# relay.net
KiCad netlist of a schematic drawn in EAGLE
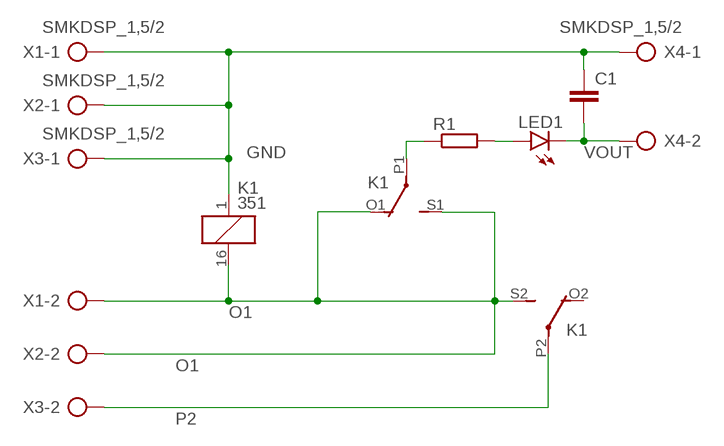
[diagram p0: schematic, sheet 1]

(export (version "E")
  (design (tool "Eeschema 10.0.6"))
  (components
    (comp (ref "C1")
      (value "C-EU025-025X050")
      (footprint "eagle-import:C025-025X050")
      (libsource (lib "eagle-import") (part "C-EU025-025X050"))
    )
    (comp (ref "K1")
      (value "351")
      (footprint "eagle-import:351")
      (libsource (lib "eagle-import") (part "351"))
    )
    (comp (ref "LED1")
      (value "LED3MM")
      (footprint "eagle-import:LED3MM")
      (libsource (lib "eagle-import") (part "LED3MM"))
    )
    (comp (ref "R1")
      (value "R-EU_0207/10")
      (footprint "eagle-import:0207_10")
      (libsource (lib "eagle-import") (part "R-EU_0207/10"))
    )
    (comp (ref "X1")
      (value "SMKDSP_1,5/2")
      (footprint "eagle-import:SMKDSP_1,5_2")
      (fields (field (name "MF") "FARNELL") (field (name "MPN") "1733570"))
      (libsource (lib "eagle-import") (part "SMKDSP_1,5/2"))
    )
    (comp (ref "X2")
      (value "SMKDSP_1,5/2")
      (footprint "eagle-import:SMKDSP_1,5_2")
      (fields (field (name "MF") "FARNELL") (field (name "MPN") "1733570"))
      (libsource (lib "eagle-import") (part "SMKDSP_1,5/2"))
    )
    (comp (ref "X3")
      (value "SMKDSP_1,5/2")
      (footprint "eagle-import:SMKDSP_1,5_2")
      (fields (field (name "MF") "FARNELL") (field (name "MPN") "1733570"))
      (libsource (lib "eagle-import") (part "SMKDSP_1,5/2"))
    )
    (comp (ref "X4")
      (value "SMKDSP_1,5/2")
      (footprint "eagle-import:SMKDSP_1,5_2")
      (fields (field (name "MF") "FARNELL") (field (name "MPN") "1733570"))
      (libsource (lib "eagle-import") (part "SMKDSP_1,5/2"))
    )
  )
  (nets
    (net (code "1") (name "/GND") (class "Default")
      (node (ref "C1") (pin "1") (pinfunction "1_1") (pintype "passive"))
      (node (ref "K1") (pin "1") (pinfunction "1_1") (pintype "passive"))
      (node (ref "X1") (pin "1") (pinfunction "KL_1") (pintype "passive"))
      (node (ref "X2") (pin "1") (pinfunction "KL_1") (pintype "passive"))
      (node (ref "X3") (pin "1") (pinfunction "KL_1") (pintype "passive"))
      (node (ref "X4") (pin "1") (pinfunction "KL_1") (pintype "passive"))
    )
    (net (code "2") (name "/O1") (class "Default")
      (node (ref "K1") (pin "16") (pinfunction "2_16") (pintype "passive"))
      (node (ref "K1") (pin "O1") (pinfunction "O_O1") (pintype "passive"))
      (node (ref "K1") (pin "S1") (pinfunction "S_S1") (pintype "passive"))
      (node (ref "K1") (pin "S2") (pinfunction "S_S2") (pintype "passive"))
      (node (ref "X1") (pin "2") (pinfunction "KL_2") (pintype "passive"))
      (node (ref "X2") (pin "2") (pinfunction "KL_2") (pintype "passive"))
    )
    (net (code "3") (name "/P2") (class "Default")
      (node (ref "K1") (pin "P2") (pinfunction "P_P2") (pintype "passive"))
      (node (ref "X3") (pin "2") (pinfunction "KL_2") (pintype "passive"))
    )
    (net (code "4") (name "/VOUT") (class "Default")
      (node (ref "C1") (pin "2") (pinfunction "2_2") (pintype "passive"))
      (node (ref "LED1") (pin "K") (pinfunction "C_K") (pintype "passive"))
      (node (ref "X4") (pin "2") (pinfunction "KL_2") (pintype "passive"))
    )
    (net (code "5") (name "Net-(K1B-P)") (class "Default")
      (node (ref "K1") (pin "P1") (pinfunction "P_P1") (pintype "passive"))
      (node (ref "R1") (pin "1") (pinfunction "1_1") (pintype "passive"))
    )
    (net (code "6") (name "Net-(LED1-PadA)") (class "Default")
      (node (ref "LED1") (pin "A") (pinfunction "A_A") (pintype "passive"))
      (node (ref "R1") (pin "2") (pinfunction "2_2") (pintype "passive"))
    )
    (net (code "7") (name "unconnected-(K1C-O-PadO2)") (class "Default")
      (node (ref "K1") (pin "O2") (pinfunction "O_O2") (pintype "passive"))
    )
  )
)
